# PCB_Segment_Shift_Reg.net
KiCad netlist of a schematic drawn in Altium Designer
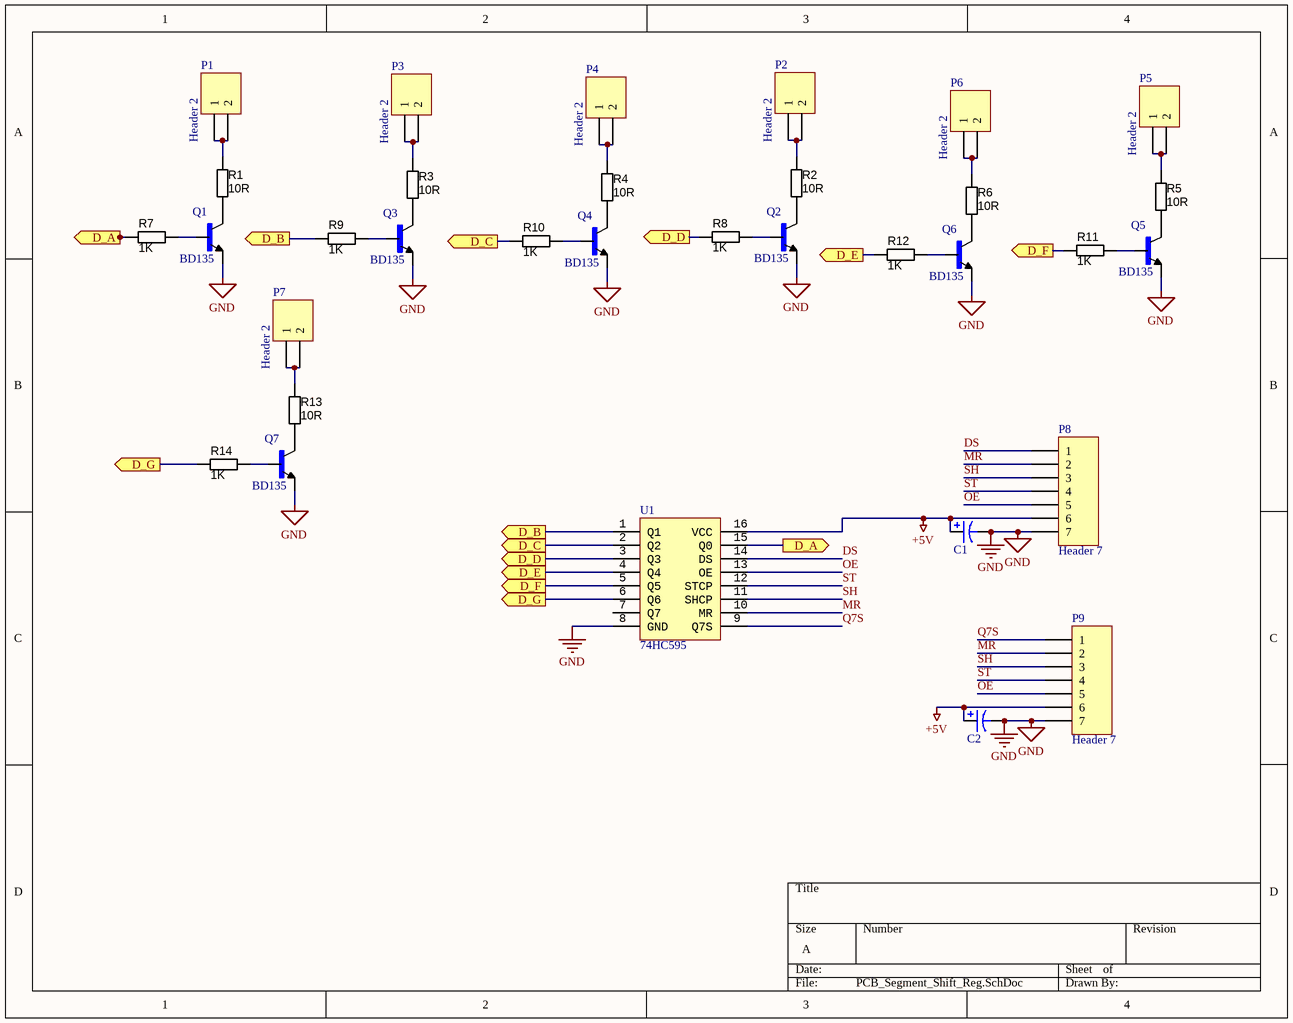
[diagram p0: PCB_Segment_Shift_Reg.SchDoc]

(export (version "E")
  (design (tool "Eeschema 10.0.6"))
  (components
    (comp (ref "C1")
      (value "100 μF")
      (footprint "CAPE10.0MM_Rad_10x14mm")
      (description "Electrolitic Capacitor, Thru-Hole")
      (fields
        (field (name "PUBLISHER") "Cynetik Group")
        (field (name "CREATED BY") "Zion Blue")
        (field (name "CONTACT") "cynetik_group@hotmail.com")
      )
      (libsource (lib "Capacitors") (part "Electrolitic Capacitor, Thru-Hole"))
    )
    (comp (ref "C2")
      (value "100 μF")
      (footprint "CAPE10.0MM_Rad_10x14mm")
      (description "Electrolitic Capacitor, Thru-Hole")
      (fields
        (field (name "PUBLISHER") "Cynetik Group")
        (field (name "CREATED BY") "Zion Blue")
        (field (name "CONTACT") "cynetik_group@hotmail.com")
      )
      (libsource (lib "Capacitors") (part "Electrolitic Capacitor, Thru-Hole"))
    )
    (comp (ref "P1")
      (value "Header 2")
      (footprint "HDR1X2")
      (description "Header, 2-Pin")
      (fields (field (name "PUBLISHER") "Altium Limited"))
      (libsource (lib "Miscellaneous Connectors") (part "Header 2"))
    )
    (comp (ref "P2")
      (value "Header 2")
      (footprint "HDR1X2")
      (description "Header, 2-Pin")
      (fields (field (name "PUBLISHER") "Altium Limited"))
      (libsource (lib "Miscellaneous Connectors") (part "Header 2"))
    )
    (comp (ref "P3")
      (value "Header 2")
      (footprint "HDR1X2")
      (description "Header, 2-Pin")
      (fields (field (name "PUBLISHER") "Altium Limited"))
      (libsource (lib "Miscellaneous Connectors") (part "Header 2"))
    )
    (comp (ref "P4")
      (value "Header 2")
      (footprint "HDR1X2")
      (description "Header, 2-Pin")
      (fields (field (name "PUBLISHER") "Altium Limited"))
      (libsource (lib "Miscellaneous Connectors") (part "Header 2"))
    )
    (comp (ref "P5")
      (value "Header 2")
      (footprint "HDR1X2")
      (description "Header, 2-Pin")
      (fields (field (name "PUBLISHER") "Altium Limited"))
      (libsource (lib "Miscellaneous Connectors") (part "Header 2"))
    )
    (comp (ref "P6")
      (value "Header 2")
      (footprint "HDR1X2")
      (description "Header, 2-Pin")
      (fields (field (name "PUBLISHER") "Altium Limited"))
      (libsource (lib "Miscellaneous Connectors") (part "Header 2"))
    )
    (comp (ref "P7")
      (value "Header 2")
      (footprint "HDR1X2")
      (description "Header, 2-Pin")
      (fields (field (name "PUBLISHER") "Altium Limited"))
      (libsource (lib "Miscellaneous Connectors") (part "Header 2"))
    )
    (comp (ref "P8")
      (value "Header 7")
      (footprint "HDR1X7")
      (description "Header, 7-Pin")
      (fields (field (name "PUBLISHER") "Altium Limited"))
      (libsource (lib "Miscellaneous Connectors") (part "Header 7"))
    )
    (comp (ref "P9")
      (value "Header 7")
      (footprint "HDR1X7")
      (description "Header, 7-Pin")
      (fields (field (name "PUBLISHER") "Altium Limited"))
      (libsource (lib "Miscellaneous Connectors") (part "Header 7"))
    )
    (comp (ref "Q1")
      (value "BD135")
      (footprint "*TO229P780X300X2000-3 - duplicate")
      (description "Trans GP BJT NPN 45V 1.5A 3-Pin TO-126")
      (fields (field (name "MF") "ON Semiconductor"))
      (libsource (lib "BD135") (part "BD135"))
    )
    (comp (ref "Q2")
      (value "BD135")
      (footprint "*TO229P780X300X2000-3 - duplicate")
      (description "Trans GP BJT NPN 45V 1.5A 3-Pin TO-126")
      (fields (field (name "MF") "ON Semiconductor"))
      (libsource (lib "BD135") (part "BD135"))
    )
    (comp (ref "Q3")
      (value "BD135")
      (footprint "*TO229P780X300X2000-3 - duplicate")
      (description "Trans GP BJT NPN 45V 1.5A 3-Pin TO-126")
      (fields (field (name "MF") "ON Semiconductor"))
      (libsource (lib "BD135") (part "BD135"))
    )
    (comp (ref "Q4")
      (value "BD135")
      (footprint "*TO229P780X300X2000-3 - duplicate")
      (description "Trans GP BJT NPN 45V 1.5A 3-Pin TO-126")
      (fields (field (name "MF") "ON Semiconductor"))
      (libsource (lib "BD135") (part "BD135"))
    )
    (comp (ref "Q5")
      (value "BD135")
      (footprint "*TO229P780X300X2000-3 - duplicate")
      (description "Trans GP BJT NPN 45V 1.5A 3-Pin TO-126")
      (fields (field (name "MF") "ON Semiconductor"))
      (libsource (lib "BD135") (part "BD135"))
    )
    (comp (ref "Q6")
      (value "BD135")
      (footprint "*TO229P780X300X2000-3 - duplicate")
      (description "Trans GP BJT NPN 45V 1.5A 3-Pin TO-126")
      (fields (field (name "MF") "ON Semiconductor"))
      (libsource (lib "BD135") (part "BD135"))
    )
    (comp (ref "Q7")
      (value "BD135")
      (footprint "*TO229P780X300X2000-3 - duplicate")
      (description "Trans GP BJT NPN 45V 1.5A 3-Pin TO-126")
      (fields (field (name "MF") "ON Semiconductor"))
      (libsource (lib "BD135") (part "BD135"))
    )
    (comp (ref "R1")
      (value "10R")
      (footprint "AXIAL-0.6")
      (description "Resistor THD 10 Ohm 1W 5% Metal Film")
      (fields (field (name "TOLERANCE") "±5%") (field (name "Comment") "Metal Film"))
      (libsource (lib "PBL - Resistors") (part "RES_10R_Axial_1W_5%"))
    )
    (comp (ref "R2")
      (value "10R")
      (footprint "AXIAL-0.6")
      (description "Resistor THD 10 Ohm 1W 5% Metal Film")
      (fields (field (name "TOLERANCE") "±5%") (field (name "Comment") "Metal Film"))
      (libsource (lib "PBL - Resistors") (part "RES_10R_Axial_1W_5%"))
    )
    (comp (ref "R3")
      (value "10R")
      (footprint "AXIAL-0.6")
      (description "Resistor THD 10 Ohm 1W 5% Metal Film")
      (fields (field (name "TOLERANCE") "±5%") (field (name "Comment") "Metal Film"))
      (libsource (lib "PBL - Resistors") (part "RES_10R_Axial_1W_5%"))
    )
    (comp (ref "R4")
      (value "10R")
      (footprint "AXIAL-0.6")
      (description "Resistor THD 10 Ohm 1W 5% Metal Film")
      (fields (field (name "TOLERANCE") "±5%") (field (name "Comment") "Metal Film"))
      (libsource (lib "PBL - Resistors") (part "RES_10R_Axial_1W_5%"))
    )
    (comp (ref "R5")
      (value "10R")
      (footprint "AXIAL-0.6")
      (description "Resistor THD 10 Ohm 1W 5% Metal Film")
      (fields (field (name "TOLERANCE") "±5%") (field (name "Comment") "Metal Film"))
      (libsource (lib "PBL - Resistors") (part "RES_10R_Axial_1W_5%"))
    )
    (comp (ref "R6")
      (value "10R")
      (footprint "AXIAL-0.6")
      (description "Resistor THD 10 Ohm 1W 5% Metal Film")
      (fields (field (name "TOLERANCE") "±5%") (field (name "Comment") "Metal Film"))
      (libsource (lib "PBL - Resistors") (part "RES_10R_Axial_1W_5%"))
    )
    (comp (ref "R7")
      (value "1K")
      (footprint "RESTH_AXIAL-0.4")
      (description "Resistor THD Axial 1k Ohm 0.25W 5% Carbon Film")
      (fields (field (name "TOLERANCE") "±5%") (field (name "Comment") "Carbon Film"))
      (libsource (lib "PBL - Resistors") (part "RES_1K_Axial_0.25W_5%"))
    )
    (comp (ref "R8")
      (value "1K")
      (footprint "RESTH_AXIAL-0.4")
      (description "Resistor THD Axial 1k Ohm 0.25W 5% Carbon Film")
      (fields (field (name "TOLERANCE") "±5%") (field (name "Comment") "Carbon Film"))
      (libsource (lib "PBL - Resistors") (part "RES_1K_Axial_0.25W_5%"))
    )
    (comp (ref "R9")
      (value "1K")
      (footprint "RESTH_AXIAL-0.4")
      (description "Resistor THD Axial 1k Ohm 0.25W 5% Carbon Film")
      (fields (field (name "TOLERANCE") "±5%") (field (name "Comment") "Carbon Film"))
      (libsource (lib "PBL - Resistors") (part "RES_1K_Axial_0.25W_5%"))
    )
    (comp (ref "R10")
      (value "1K")
      (footprint "RESTH_AXIAL-0.4")
      (description "Resistor THD Axial 1k Ohm 0.25W 5% Carbon Film")
      (fields (field (name "TOLERANCE") "±5%") (field (name "Comment") "Carbon Film"))
      (libsource (lib "PBL - Resistors") (part "RES_1K_Axial_0.25W_5%"))
    )
    (comp (ref "R11")
      (value "1K")
      (footprint "RESTH_AXIAL-0.4")
      (description "Resistor THD Axial 1k Ohm 0.25W 5% Carbon Film")
      (fields (field (name "TOLERANCE") "±5%") (field (name "Comment") "Carbon Film"))
      (libsource (lib "PBL - Resistors") (part "RES_1K_Axial_0.25W_5%"))
    )
    (comp (ref "R12")
      (value "1K")
      (footprint "RESTH_AXIAL-0.4")
      (description "Resistor THD Axial 1k Ohm 0.25W 5% Carbon Film")
      (fields (field (name "TOLERANCE") "±5%") (field (name "Comment") "Carbon Film"))
      (libsource (lib "PBL - Resistors") (part "RES_1K_Axial_0.25W_5%"))
    )
    (comp (ref "R13")
      (value "10R")
      (footprint "AXIAL-0.6")
      (description "Resistor THD 10 Ohm 1W 5% Metal Film")
      (fields (field (name "TOLERANCE") "±5%") (field (name "Comment") "Metal Film"))
      (libsource (lib "PBL - Resistors") (part "RES_10R_Axial_1W_5%"))
    )
    (comp (ref "R14")
      (value "1K")
      (footprint "RESTH_AXIAL-0.4")
      (description "Resistor THD Axial 1k Ohm 0.25W 5% Carbon Film")
      (fields (field (name "TOLERANCE") "±5%") (field (name "Comment") "Carbon Film"))
      (libsource (lib "PBL - Resistors") (part "RES_1K_Axial_0.25W_5%"))
    )
    (comp (ref "U1")
      (value "74HC595")
      (footprint "DIP_300_16")
      (description "74 Series")
      (libsource (lib "ICs") (part "74HC595"))
    )
  )
  (nets
    (net (code "1") (name "+5V") (class "Default")
      (node (ref "C1") (pin "1") (pinfunction "1_1") (pintype "passive"))
      (node (ref "C2") (pin "1") (pinfunction "1_1") (pintype "passive"))
      (node (ref "P8") (pin "6") (pinfunction "6_6") (pintype "passive"))
      (node (ref "P9") (pin "6") (pinfunction "6_6") (pintype "passive"))
      (node (ref "U1") (pin "16") (pinfunction "VCC_16") (pintype "passive"))
    )
    (net (code "2") (name "/DS") (class "Default")
      (node (ref "P8") (pin "1") (pinfunction "1_1") (pintype "passive"))
      (node (ref "U1") (pin "14") (pinfunction "DS_14") (pintype "passive"))
    )
    (net (code "3") (name "/D_A") (class "Default")
      (node (ref "R7") (pin "1") (pinfunction "1_1") (pintype "passive"))
      (node (ref "U1") (pin "15") (pinfunction "Q0_15") (pintype "passive"))
    )
    (net (code "4") (name "/D_B") (class "Default")
      (node (ref "R9") (pin "1") (pinfunction "1_1") (pintype "passive"))
      (node (ref "U1") (pin "1") (pinfunction "Q1_1") (pintype "passive"))
    )
    (net (code "5") (name "/D_C") (class "Default")
      (node (ref "R10") (pin "1") (pinfunction "1_1") (pintype "passive"))
      (node (ref "U1") (pin "2") (pinfunction "Q2_2") (pintype "passive"))
    )
    (net (code "6") (name "/D_D") (class "Default")
      (node (ref "R8") (pin "1") (pinfunction "1_1") (pintype "passive"))
      (node (ref "U1") (pin "3") (pinfunction "Q3_3") (pintype "passive"))
    )
    (net (code "7") (name "/D_E") (class "Default")
      (node (ref "R12") (pin "1") (pinfunction "1_1") (pintype "passive"))
      (node (ref "U1") (pin "4") (pinfunction "Q4_4") (pintype "passive"))
    )
    (net (code "8") (name "/D_F") (class "Default")
      (node (ref "R11") (pin "1") (pinfunction "1_1") (pintype "passive"))
      (node (ref "U1") (pin "5") (pinfunction "Q5_5") (pintype "passive"))
    )
    (net (code "9") (name "/D_G") (class "Default")
      (node (ref "R14") (pin "1") (pinfunction "1_1") (pintype "passive"))
      (node (ref "U1") (pin "6") (pinfunction "Q6_6") (pintype "passive"))
    )
    (net (code "10") (name "/MR") (class "Default")
      (node (ref "P8") (pin "2") (pinfunction "2_2") (pintype "passive"))
      (node (ref "P9") (pin "2") (pinfunction "2_2") (pintype "passive"))
      (node (ref "U1") (pin "10") (pinfunction "MR_10") (pintype "passive"))
    )
    (net (code "11") (name "/OE") (class "Default")
      (node (ref "P8") (pin "5") (pinfunction "5_5") (pintype "passive"))
      (node (ref "P9") (pin "5") (pinfunction "5_5") (pintype "passive"))
      (node (ref "U1") (pin "13") (pinfunction "OE_13") (pintype "passive"))
    )
    (net (code "12") (name "/Q7S") (class "Default")
      (node (ref "P9") (pin "1") (pinfunction "1_1") (pintype "passive"))
      (node (ref "U1") (pin "9") (pinfunction "Q7S_9") (pintype "passive"))
    )
    (net (code "13") (name "/SH") (class "Default")
      (node (ref "P8") (pin "3") (pinfunction "3_3") (pintype "passive"))
      (node (ref "P9") (pin "3") (pinfunction "3_3") (pintype "passive"))
      (node (ref "U1") (pin "11") (pinfunction "SHCP_11") (pintype "passive"))
    )
    (net (code "14") (name "/ST") (class "Default")
      (node (ref "P8") (pin "4") (pinfunction "4_4") (pintype "passive"))
      (node (ref "P9") (pin "4") (pinfunction "4_4") (pintype "passive"))
      (node (ref "U1") (pin "12") (pinfunction "STCP_12") (pintype "passive"))
    )
    (net (code "15") (name "GND") (class "Default")
      (node (ref "C1") (pin "2") (pinfunction "2_2") (pintype "passive"))
      (node (ref "C2") (pin "2") (pinfunction "2_2") (pintype "passive"))
      (node (ref "P8") (pin "7") (pinfunction "7_7") (pintype "passive"))
      (node (ref "P9") (pin "7") (pinfunction "7_7") (pintype "passive"))
      (node (ref "Q1") (pin "1") (pinfunction "E_1") (pintype "passive"))
      (node (ref "Q2") (pin "1") (pinfunction "E_1") (pintype "passive"))
      (node (ref "Q3") (pin "1") (pinfunction "E_1") (pintype "passive"))
      (node (ref "Q4") (pin "1") (pinfunction "E_1") (pintype "passive"))
      (node (ref "Q5") (pin "1") (pinfunction "E_1") (pintype "passive"))
      (node (ref "Q6") (pin "1") (pinfunction "E_1") (pintype "passive"))
      (node (ref "Q7") (pin "1") (pinfunction "E_1") (pintype "passive"))
      (node (ref "U1") (pin "8") (pinfunction "GND_8") (pintype "passive"))
    )
    (net (code "16") (name "Net-(P1-Pad1)") (class "Default")
      (node (ref "P1") (pin "1") (pinfunction "1_1") (pintype "passive"))
      (node (ref "P1") (pin "2") (pinfunction "2_2") (pintype "passive"))
      (node (ref "R1") (pin "1") (pinfunction "1_1") (pintype "passive"))
    )
    (net (code "17") (name "Net-(P2-Pad1)") (class "Default")
      (node (ref "P2") (pin "1") (pinfunction "1_1") (pintype "passive"))
      (node (ref "P2") (pin "2") (pinfunction "2_2") (pintype "passive"))
      (node (ref "R2") (pin "1") (pinfunction "1_1") (pintype "passive"))
    )
    (net (code "18") (name "Net-(P3-Pad1)") (class "Default")
      (node (ref "P3") (pin "1") (pinfunction "1_1") (pintype "passive"))
      (node (ref "P3") (pin "2") (pinfunction "2_2") (pintype "passive"))
      (node (ref "R3") (pin "1") (pinfunction "1_1") (pintype "passive"))
    )
    (net (code "19") (name "Net-(P4-Pad1)") (class "Default")
      (node (ref "P4") (pin "1") (pinfunction "1_1") (pintype "passive"))
      (node (ref "P4") (pin "2") (pinfunction "2_2") (pintype "passive"))
      (node (ref "R4") (pin "1") (pinfunction "1_1") (pintype "passive"))
    )
    (net (code "20") (name "Net-(P5-Pad1)") (class "Default")
      (node (ref "P5") (pin "1") (pinfunction "1_1") (pintype "passive"))
      (node (ref "P5") (pin "2") (pinfunction "2_2") (pintype "passive"))
      (node (ref "R5") (pin "1") (pinfunction "1_1") (pintype "passive"))
    )
    (net (code "21") (name "Net-(P6-Pad1)") (class "Default")
      (node (ref "P6") (pin "1") (pinfunction "1_1") (pintype "passive"))
      (node (ref "P6") (pin "2") (pinfunction "2_2") (pintype "passive"))
      (node (ref "R6") (pin "1") (pinfunction "1_1") (pintype "passive"))
    )
    (net (code "22") (name "Net-(P7-Pad1)") (class "Default")
      (node (ref "P7") (pin "1") (pinfunction "1_1") (pintype "passive"))
      (node (ref "P7") (pin "2") (pinfunction "2_2") (pintype "passive"))
      (node (ref "R13") (pin "1") (pinfunction "1_1") (pintype "passive"))
    )
    (net (code "23") (name "Net-(Q1-B)") (class "Default")
      (node (ref "Q1") (pin "3") (pinfunction "B_3") (pintype "passive"))
      (node (ref "R7") (pin "2") (pinfunction "2_2") (pintype "passive"))
    )
    (net (code "24") (name "Net-(Q1-C)") (class "Default")
      (node (ref "Q1") (pin "2") (pinfunction "C_2") (pintype "passive"))
      (node (ref "R1") (pin "2") (pinfunction "2_2") (pintype "passive"))
    )
    (net (code "25") (name "Net-(Q2-B)") (class "Default")
      (node (ref "Q2") (pin "3") (pinfunction "B_3") (pintype "passive"))
      (node (ref "R8") (pin "2") (pinfunction "2_2") (pintype "passive"))
    )
    (net (code "26") (name "Net-(Q2-C)") (class "Default")
      (node (ref "Q2") (pin "2") (pinfunction "C_2") (pintype "passive"))
      (node (ref "R2") (pin "2") (pinfunction "2_2") (pintype "passive"))
    )
    (net (code "27") (name "Net-(Q3-B)") (class "Default")
      (node (ref "Q3") (pin "3") (pinfunction "B_3") (pintype "passive"))
      (node (ref "R9") (pin "2") (pinfunction "2_2") (pintype "passive"))
    )
    (net (code "28") (name "Net-(Q3-C)") (class "Default")
      (node (ref "Q3") (pin "2") (pinfunction "C_2") (pintype "passive"))
      (node (ref "R3") (pin "2") (pinfunction "2_2") (pintype "passive"))
    )
    (net (code "29") (name "Net-(Q4-B)") (class "Default")
      (node (ref "Q4") (pin "3") (pinfunction "B_3") (pintype "passive"))
      (node (ref "R10") (pin "2") (pinfunction "2_2") (pintype "passive"))
    )
    (net (code "30") (name "Net-(Q4-C)") (class "Default")
      (node (ref "Q4") (pin "2") (pinfunction "C_2") (pintype "passive"))
      (node (ref "R4") (pin "2") (pinfunction "2_2") (pintype "passive"))
    )
    (net (code "31") (name "Net-(Q5-B)") (class "Default")
      (node (ref "Q5") (pin "3") (pinfunction "B_3") (pintype "passive"))
      (node (ref "R11") (pin "2") (pinfunction "2_2") (pintype "passive"))
    )
    (net (code "32") (name "Net-(Q5-C)") (class "Default")
      (node (ref "Q5") (pin "2") (pinfunction "C_2") (pintype "passive"))
      (node (ref "R5") (pin "2") (pinfunction "2_2") (pintype "passive"))
    )
    (net (code "33") (name "Net-(Q6-B)") (class "Default")
      (node (ref "Q6") (pin "3") (pinfunction "B_3") (pintype "passive"))
      (node (ref "R12") (pin "2") (pinfunction "2_2") (pintype "passive"))
    )
    (net (code "34") (name "Net-(Q6-C)") (class "Default")
      (node (ref "Q6") (pin "2") (pinfunction "C_2") (pintype "passive"))
      (node (ref "R6") (pin "2") (pinfunction "2_2") (pintype "passive"))
    )
    (net (code "35") (name "Net-(Q7-B)") (class "Default")
      (node (ref "Q7") (pin "3") (pinfunction "B_3") (pintype "passive"))
      (node (ref "R14") (pin "2") (pinfunction "2_2") (pintype "passive"))
    )
    (net (code "36") (name "Net-(Q7-C)") (class "Default")
      (node (ref "Q7") (pin "2") (pinfunction "C_2") (pintype "passive"))
      (node (ref "R13") (pin "2") (pinfunction "2_2") (pintype "passive"))
    )
    (net (code "37") (name "unconnected-(U1-Q7-Pad7)") (class "Default")
      (node (ref "U1") (pin "7") (pinfunction "Q7_7") (pintype "passive"))
    )
  )
)
